# 17_FE_PORT_17-24.net
KiCad netlist of a schematic drawn in Altium Designer
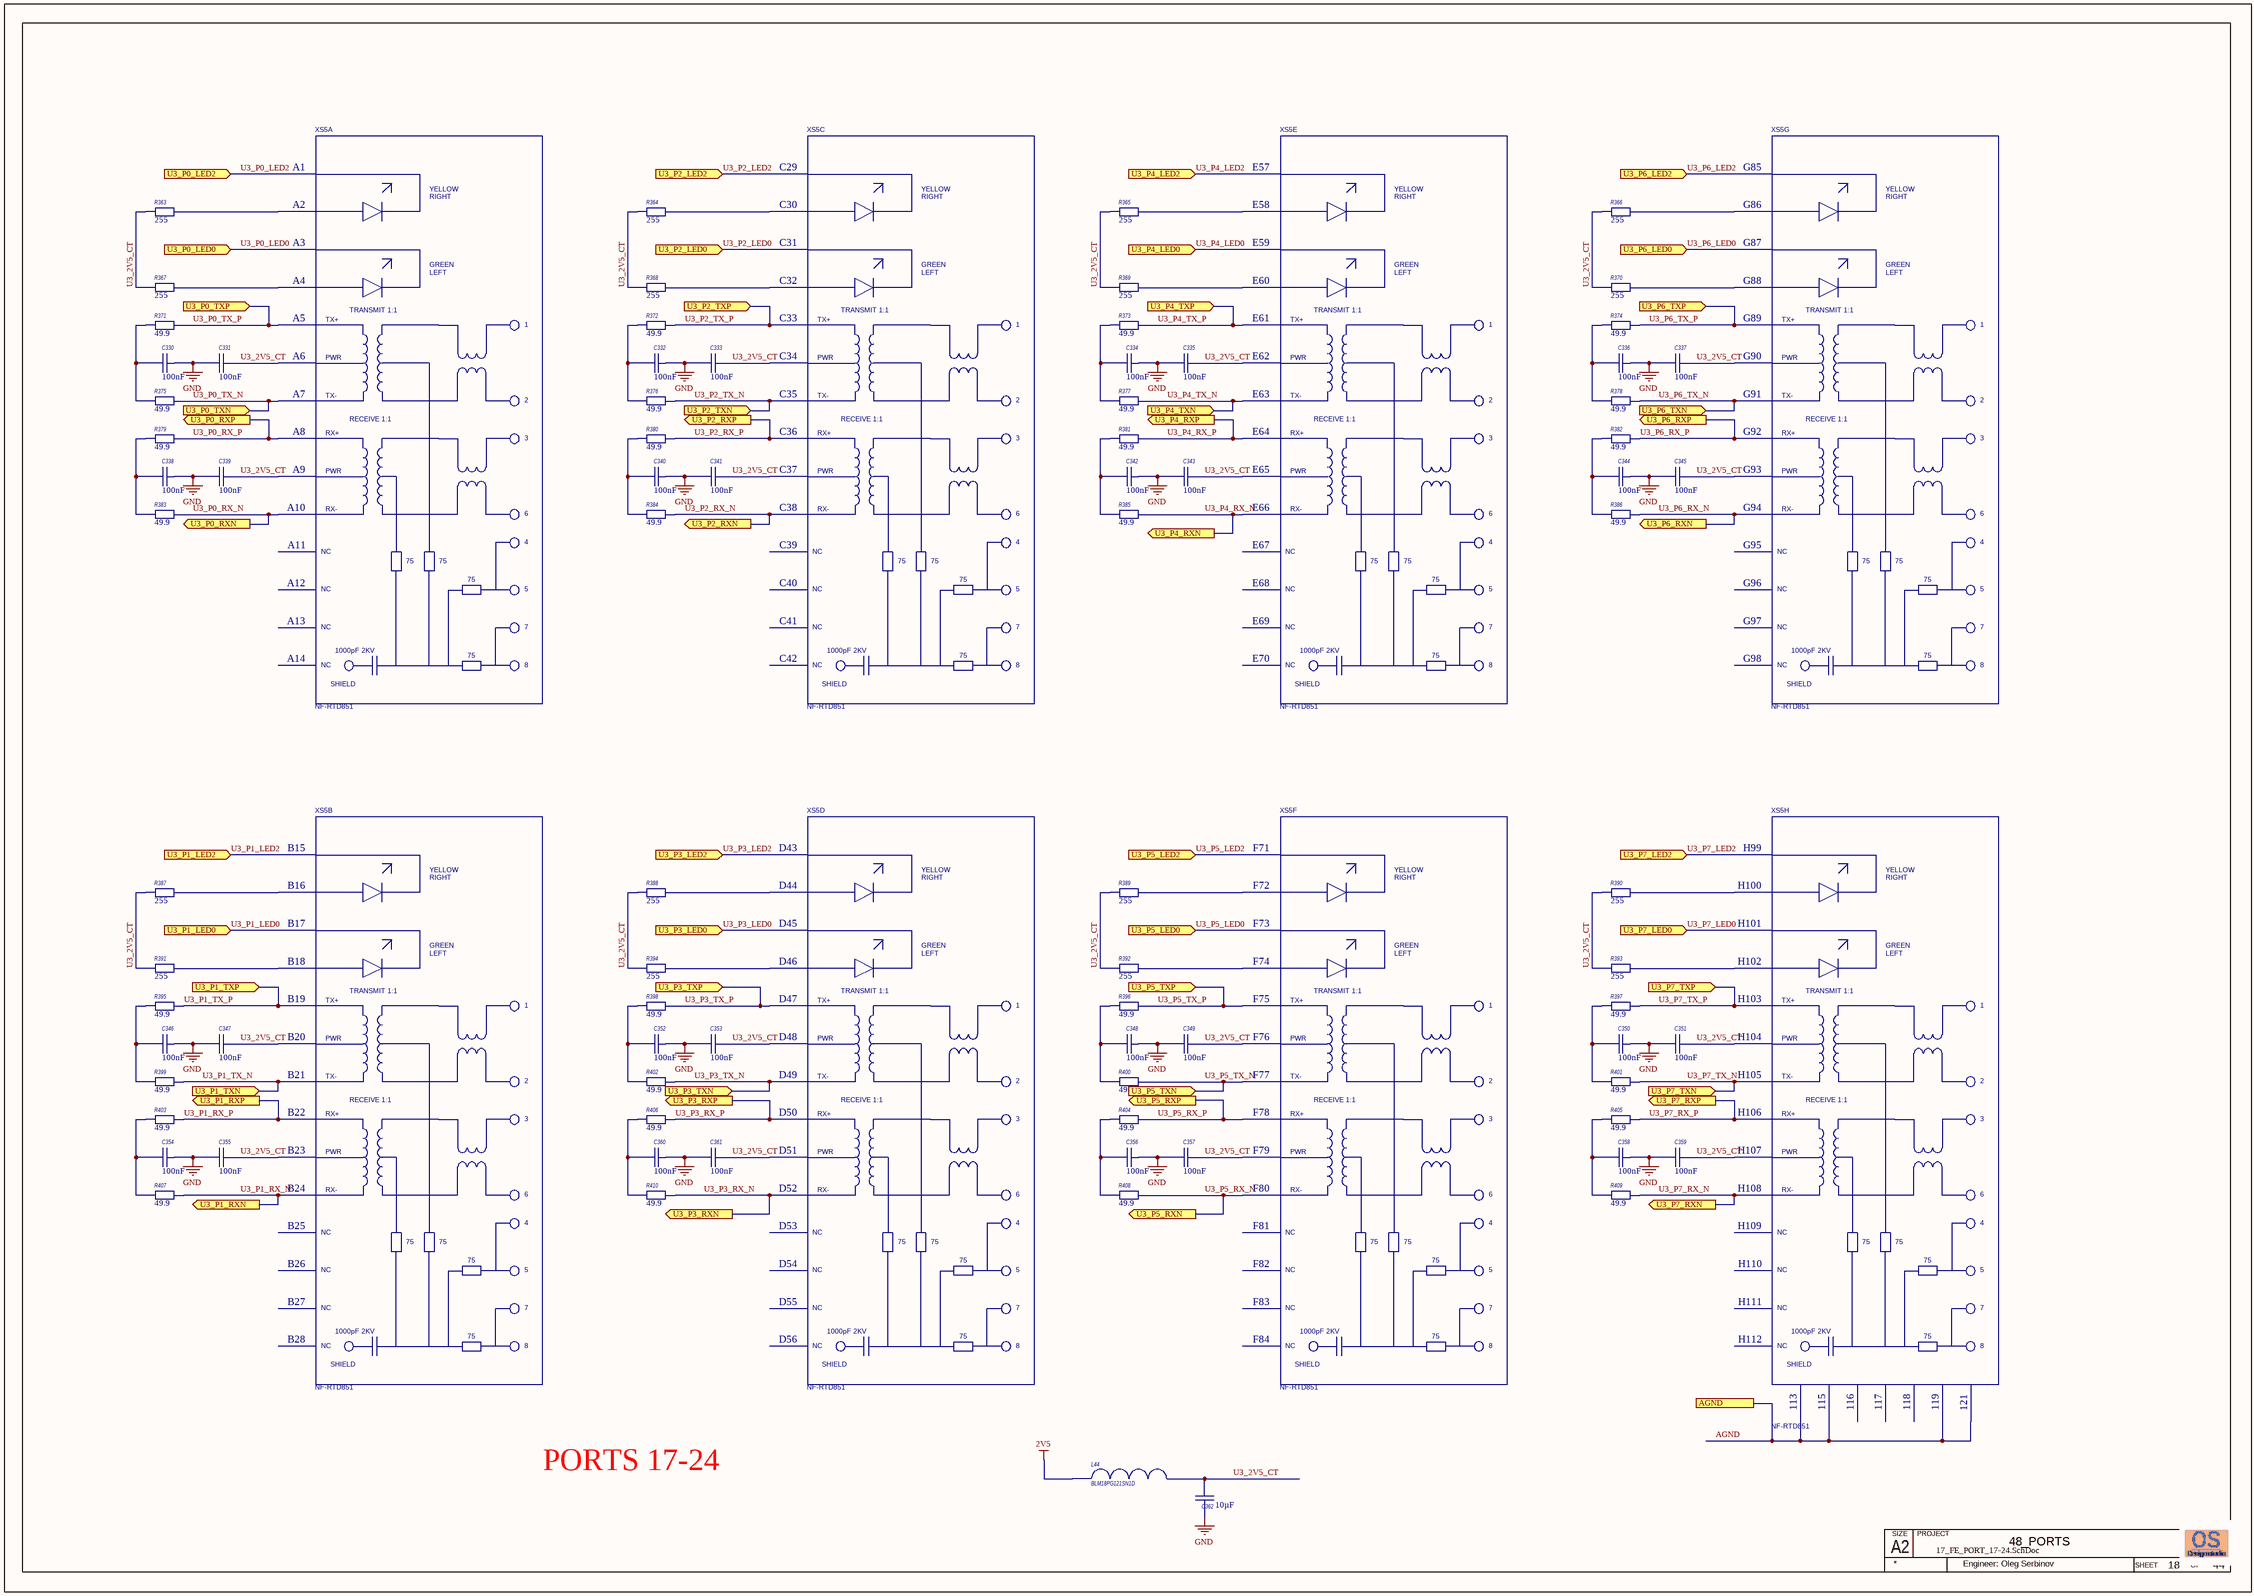
[diagram p0: 17_FE_PORT_17-24.SchDoc]

(export (version "E")
  (design (tool "Eeschema 10.0.6"))
  (components
    (comp (ref "C330")
      (value "GRM155R71E104KE14D")
      (footprint "C0402_IPC High Density")
      (description "C0402, 100nF, 25V, X7R")
      (fields
        (field (name "MANUFACTURER") "Murata")
        (field (name "CAPACITANCE") "100nF")
        (field (name "CUSTOMER PART NUMBER") "Конденсатор, 100n, 0402, 25V, X7R, 10%")
      )
      (libsource (lib "CAPACITORS") (part "GRM155R71E104KE14D"))
    )
    (comp (ref "C331")
      (value "GRM155R71E104KE14D")
      (footprint "C0402_IPC High Density")
      (description "C0402, 100nF, 25V, X7R")
      (fields
        (field (name "MANUFACTURER") "Murata")
        (field (name "CAPACITANCE") "100nF")
        (field (name "CUSTOMER PART NUMBER") "Конденсатор, 100n, 0402, 25V, X7R, 10%")
      )
      (libsource (lib "CAPACITORS") (part "GRM155R71E104KE14D"))
    )
    (comp (ref "C332")
      (value "GRM155R71E104KE14D")
      (footprint "C0402_IPC High Density")
      (description "C0402, 100nF, 25V, X7R")
      (fields
        (field (name "MANUFACTURER") "Murata")
        (field (name "CAPACITANCE") "100nF")
        (field (name "CUSTOMER PART NUMBER") "Конденсатор, 100n, 0402, 25V, X7R, 10%")
      )
      (libsource (lib "CAPACITORS") (part "GRM155R71E104KE14D"))
    )
    (comp (ref "C333")
      (value "GRM155R71E104KE14D")
      (footprint "C0402_IPC High Density")
      (description "C0402, 100nF, 25V, X7R")
      (fields
        (field (name "MANUFACTURER") "Murata")
        (field (name "CAPACITANCE") "100nF")
        (field (name "CUSTOMER PART NUMBER") "Конденсатор, 100n, 0402, 25V, X7R, 10%")
      )
      (libsource (lib "CAPACITORS") (part "GRM155R71E104KE14D"))
    )
    (comp (ref "C334")
      (value "GRM155R71E104KE14D")
      (footprint "C0402_IPC High Density")
      (description "C0402, 100nF, 25V, X7R")
      (fields
        (field (name "MANUFACTURER") "Murata")
        (field (name "CAPACITANCE") "100nF")
        (field (name "CUSTOMER PART NUMBER") "Конденсатор, 100n, 0402, 25V, X7R, 10%")
      )
      (libsource (lib "CAPACITORS") (part "GRM155R71E104KE14D"))
    )
    (comp (ref "C335")
      (value "GRM155R71E104KE14D")
      (footprint "C0402_IPC High Density")
      (description "C0402, 100nF, 25V, X7R")
      (fields
        (field (name "MANUFACTURER") "Murata")
        (field (name "CAPACITANCE") "100nF")
        (field (name "CUSTOMER PART NUMBER") "Конденсатор, 100n, 0402, 25V, X7R, 10%")
      )
      (libsource (lib "CAPACITORS") (part "GRM155R71E104KE14D"))
    )
    (comp (ref "C336")
      (value "GRM155R71E104KE14D")
      (footprint "C0402_IPC High Density")
      (description "C0402, 100nF, 25V, X7R")
      (fields
        (field (name "MANUFACTURER") "Murata")
        (field (name "CAPACITANCE") "100nF")
        (field (name "CUSTOMER PART NUMBER") "Конденсатор, 100n, 0402, 25V, X7R, 10%")
      )
      (libsource (lib "CAPACITORS") (part "GRM155R71E104KE14D"))
    )
    (comp (ref "C337")
      (value "GRM155R71E104KE14D")
      (footprint "C0402_IPC High Density")
      (description "C0402, 100nF, 25V, X7R")
      (fields
        (field (name "MANUFACTURER") "Murata")
        (field (name "CAPACITANCE") "100nF")
        (field (name "CUSTOMER PART NUMBER") "Конденсатор, 100n, 0402, 25V, X7R, 10%")
      )
      (libsource (lib "CAPACITORS") (part "GRM155R71E104KE14D"))
    )
    (comp (ref "C338")
      (value "GRM155R71E104KE14D")
      (footprint "C0402_IPC High Density")
      (description "C0402, 100nF, 25V, X7R")
      (fields
        (field (name "MANUFACTURER") "Murata")
        (field (name "CAPACITANCE") "100nF")
        (field (name "CUSTOMER PART NUMBER") "Конденсатор, 100n, 0402, 25V, X7R, 10%")
      )
      (libsource (lib "CAPACITORS") (part "GRM155R71E104KE14D"))
    )
    (comp (ref "C339")
      (value "GRM155R71E104KE14D")
      (footprint "C0402_IPC High Density")
      (description "C0402, 100nF, 25V, X7R")
      (fields
        (field (name "MANUFACTURER") "Murata")
        (field (name "CAPACITANCE") "100nF")
        (field (name "CUSTOMER PART NUMBER") "Конденсатор, 100n, 0402, 25V, X7R, 10%")
      )
      (libsource (lib "CAPACITORS") (part "GRM155R71E104KE14D"))
    )
    (comp (ref "C340")
      (value "GRM155R71E104KE14D")
      (footprint "C0402_IPC High Density")
      (description "C0402, 100nF, 25V, X7R")
      (fields
        (field (name "MANUFACTURER") "Murata")
        (field (name "CAPACITANCE") "100nF")
        (field (name "CUSTOMER PART NUMBER") "Конденсатор, 100n, 0402, 25V, X7R, 10%")
      )
      (libsource (lib "CAPACITORS") (part "GRM155R71E104KE14D"))
    )
    (comp (ref "C341")
      (value "GRM155R71E104KE14D")
      (footprint "C0402_IPC High Density")
      (description "C0402, 100nF, 25V, X7R")
      (fields
        (field (name "MANUFACTURER") "Murata")
        (field (name "CAPACITANCE") "100nF")
        (field (name "CUSTOMER PART NUMBER") "Конденсатор, 100n, 0402, 25V, X7R, 10%")
      )
      (libsource (lib "CAPACITORS") (part "GRM155R71E104KE14D"))
    )
    (comp (ref "C342")
      (value "GRM155R71E104KE14D")
      (footprint "C0402_IPC High Density")
      (description "C0402, 100nF, 25V, X7R")
      (fields
        (field (name "MANUFACTURER") "Murata")
        (field (name "CAPACITANCE") "100nF")
        (field (name "CUSTOMER PART NUMBER") "Конденсатор, 100n, 0402, 25V, X7R, 10%")
      )
      (libsource (lib "CAPACITORS") (part "GRM155R71E104KE14D"))
    )
    (comp (ref "C343")
      (value "GRM155R71E104KE14D")
      (footprint "C0402_IPC High Density")
      (description "C0402, 100nF, 25V, X7R")
      (fields
        (field (name "MANUFACTURER") "Murata")
        (field (name "CAPACITANCE") "100nF")
        (field (name "CUSTOMER PART NUMBER") "Конденсатор, 100n, 0402, 25V, X7R, 10%")
      )
      (libsource (lib "CAPACITORS") (part "GRM155R71E104KE14D"))
    )
    (comp (ref "C344")
      (value "GRM155R71E104KE14D")
      (footprint "C0402_IPC High Density")
      (description "C0402, 100nF, 25V, X7R")
      (fields
        (field (name "MANUFACTURER") "Murata")
        (field (name "CAPACITANCE") "100nF")
        (field (name "CUSTOMER PART NUMBER") "Конденсатор, 100n, 0402, 25V, X7R, 10%")
      )
      (libsource (lib "CAPACITORS") (part "GRM155R71E104KE14D"))
    )
    (comp (ref "C345")
      (value "GRM155R71E104KE14D")
      (footprint "C0402_IPC High Density")
      (description "C0402, 100nF, 25V, X7R")
      (fields
        (field (name "MANUFACTURER") "Murata")
        (field (name "CAPACITANCE") "100nF")
        (field (name "CUSTOMER PART NUMBER") "Конденсатор, 100n, 0402, 25V, X7R, 10%")
      )
      (libsource (lib "CAPACITORS") (part "GRM155R71E104KE14D"))
    )
    (comp (ref "C346")
      (value "GRM155R71E104KE14D")
      (footprint "C0402_IPC High Density")
      (description "C0402, 100nF, 25V, X7R")
      (fields
        (field (name "MANUFACTURER") "Murata")
        (field (name "CAPACITANCE") "100nF")
        (field (name "CUSTOMER PART NUMBER") "Конденсатор, 100n, 0402, 25V, X7R, 10%")
      )
      (libsource (lib "CAPACITORS") (part "GRM155R71E104KE14D"))
    )
    (comp (ref "C347")
      (value "GRM155R71E104KE14D")
      (footprint "C0402_IPC High Density")
      (description "C0402, 100nF, 25V, X7R")
      (fields
        (field (name "MANUFACTURER") "Murata")
        (field (name "CAPACITANCE") "100nF")
        (field (name "CUSTOMER PART NUMBER") "Конденсатор, 100n, 0402, 25V, X7R, 10%")
      )
      (libsource (lib "CAPACITORS") (part "GRM155R71E104KE14D"))
    )
    (comp (ref "C348")
      (value "GRM155R71E104KE14D")
      (footprint "C0402_IPC High Density")
      (description "C0402, 100nF, 25V, X7R")
      (fields
        (field (name "MANUFACTURER") "Murata")
        (field (name "CAPACITANCE") "100nF")
        (field (name "CUSTOMER PART NUMBER") "Конденсатор, 100n, 0402, 25V, X7R, 10%")
      )
      (libsource (lib "CAPACITORS") (part "GRM155R71E104KE14D"))
    )
    (comp (ref "C349")
      (value "GRM155R71E104KE14D")
      (footprint "C0402_IPC High Density")
      (description "C0402, 100nF, 25V, X7R")
      (fields
        (field (name "MANUFACTURER") "Murata")
        (field (name "CAPACITANCE") "100nF")
        (field (name "CUSTOMER PART NUMBER") "Конденсатор, 100n, 0402, 25V, X7R, 10%")
      )
      (libsource (lib "CAPACITORS") (part "GRM155R71E104KE14D"))
    )
    (comp (ref "C350")
      (value "GRM155R71E104KE14D")
      (footprint "C0402_IPC High Density")
      (description "C0402, 100nF, 25V, X7R")
      (fields
        (field (name "MANUFACTURER") "Murata")
        (field (name "CAPACITANCE") "100nF")
        (field (name "CUSTOMER PART NUMBER") "Конденсатор, 100n, 0402, 25V, X7R, 10%")
      )
      (libsource (lib "CAPACITORS") (part "GRM155R71E104KE14D"))
    )
    (comp (ref "C351")
      (value "GRM155R71E104KE14D")
      (footprint "C0402_IPC High Density")
      (description "C0402, 100nF, 25V, X7R")
      (fields
        (field (name "MANUFACTURER") "Murata")
        (field (name "CAPACITANCE") "100nF")
        (field (name "CUSTOMER PART NUMBER") "Конденсатор, 100n, 0402, 25V, X7R, 10%")
      )
      (libsource (lib "CAPACITORS") (part "GRM155R71E104KE14D"))
    )
    (comp (ref "C352")
      (value "GRM155R71E104KE14D")
      (footprint "C0402_IPC High Density")
      (description "C0402, 100nF, 25V, X7R")
      (fields
        (field (name "MANUFACTURER") "Murata")
        (field (name "CAPACITANCE") "100nF")
        (field (name "CUSTOMER PART NUMBER") "Конденсатор, 100n, 0402, 25V, X7R, 10%")
      )
      (libsource (lib "CAPACITORS") (part "GRM155R71E104KE14D"))
    )
    (comp (ref "C353")
      (value "GRM155R71E104KE14D")
      (footprint "C0402_IPC High Density")
      (description "C0402, 100nF, 25V, X7R")
      (fields
        (field (name "MANUFACTURER") "Murata")
        (field (name "CAPACITANCE") "100nF")
        (field (name "CUSTOMER PART NUMBER") "Конденсатор, 100n, 0402, 25V, X7R, 10%")
      )
      (libsource (lib "CAPACITORS") (part "GRM155R71E104KE14D"))
    )
    (comp (ref "C354")
      (value "GRM155R71E104KE14D")
      (footprint "C0402_IPC High Density")
      (description "C0402, 100nF, 25V, X7R")
      (fields
        (field (name "MANUFACTURER") "Murata")
        (field (name "CAPACITANCE") "100nF")
        (field (name "CUSTOMER PART NUMBER") "Конденсатор, 100n, 0402, 25V, X7R, 10%")
      )
      (libsource (lib "CAPACITORS") (part "GRM155R71E104KE14D"))
    )
    (comp (ref "C355")
      (value "GRM155R71E104KE14D")
      (footprint "C0402_IPC High Density")
      (description "C0402, 100nF, 25V, X7R")
      (fields
        (field (name "MANUFACTURER") "Murata")
        (field (name "CAPACITANCE") "100nF")
        (field (name "CUSTOMER PART NUMBER") "Конденсатор, 100n, 0402, 25V, X7R, 10%")
      )
      (libsource (lib "CAPACITORS") (part "GRM155R71E104KE14D"))
    )
    (comp (ref "C356")
      (value "GRM155R71E104KE14D")
      (footprint "C0402_IPC High Density")
      (description "C0402, 100nF, 25V, X7R")
      (fields
        (field (name "MANUFACTURER") "Murata")
        (field (name "CAPACITANCE") "100nF")
        (field (name "CUSTOMER PART NUMBER") "Конденсатор, 100n, 0402, 25V, X7R, 10%")
      )
      (libsource (lib "CAPACITORS") (part "GRM155R71E104KE14D"))
    )
    (comp (ref "C357")
      (value "GRM155R71E104KE14D")
      (footprint "C0402_IPC High Density")
      (description "C0402, 100nF, 25V, X7R")
      (fields
        (field (name "MANUFACTURER") "Murata")
        (field (name "CAPACITANCE") "100nF")
        (field (name "CUSTOMER PART NUMBER") "Конденсатор, 100n, 0402, 25V, X7R, 10%")
      )
      (libsource (lib "CAPACITORS") (part "GRM155R71E104KE14D"))
    )
    (comp (ref "C358")
      (value "GRM155R71E104KE14D")
      (footprint "C0402_IPC High Density")
      (description "C0402, 100nF, 25V, X7R")
      (fields
        (field (name "MANUFACTURER") "Murata")
        (field (name "CAPACITANCE") "100nF")
        (field (name "CUSTOMER PART NUMBER") "Конденсатор, 100n, 0402, 25V, X7R, 10%")
      )
      (libsource (lib "CAPACITORS") (part "GRM155R71E104KE14D"))
    )
    (comp (ref "C359")
      (value "GRM155R71E104KE14D")
      (footprint "C0402_IPC High Density")
      (description "C0402, 100nF, 25V, X7R")
      (fields
        (field (name "MANUFACTURER") "Murata")
        (field (name "CAPACITANCE") "100nF")
        (field (name "CUSTOMER PART NUMBER") "Конденсатор, 100n, 0402, 25V, X7R, 10%")
      )
      (libsource (lib "CAPACITORS") (part "GRM155R71E104KE14D"))
    )
    (comp (ref "C360")
      (value "GRM155R71E104KE14D")
      (footprint "C0402_IPC High Density")
      (description "C0402, 100nF, 25V, X7R")
      (fields
        (field (name "MANUFACTURER") "Murata")
        (field (name "CAPACITANCE") "100nF")
        (field (name "CUSTOMER PART NUMBER") "Конденсатор, 100n, 0402, 25V, X7R, 10%")
      )
      (libsource (lib "CAPACITORS") (part "GRM155R71E104KE14D"))
    )
    (comp (ref "C361")
      (value "GRM155R71E104KE14D")
      (footprint "C0402_IPC High Density")
      (description "C0402, 100nF, 25V, X7R")
      (fields
        (field (name "MANUFACTURER") "Murata")
        (field (name "CAPACITANCE") "100nF")
        (field (name "CUSTOMER PART NUMBER") "Конденсатор, 100n, 0402, 25V, X7R, 10%")
      )
      (libsource (lib "CAPACITORS") (part "GRM155R71E104KE14D"))
    )
    (comp (ref "C362")
      (value "GRM21BR61C106KE15")
      (footprint "CAPC2012[0805]")
      (description "C0805, 10uF 10%, 16V, X5R")
      (fields
        (field (name "MANUFACTURER") "Murata")
        (field (name "TOLERANCE") "±10%")
        (field (name "CAPACITANCE") "10µF")
      )
      (libsource (lib "CAPACITORS") (part "GRM21BR61C106KE15"))
    )
    (comp (ref "L44")
      (value "BLM18PG121SN1D")
      (footprint "INDC1608X95N")
      (description "FILTER BLM18 (0603, 2A)")
      (fields
        (field (name "MANUFACTURER") "Murata")
        (field (name "RPART NUMBER") "MPZ1608S121ATAH0 ; CIC10P121NC ; MPZ1608S121ATDH5 ; BLM18PG121SH1D ; 742792625")
      )
      (libsource (lib "INDUCTORS") (part "BLM18PG121SN1D"))
    )
    (comp (ref "R363")
      (value "ERJ-2RKF2550X")
      (footprint "RESC1005[0402]")
      (description "R0402, 255R 1%")
      (fields
        (field (name "MANUFACTURER") "Panasonic")
        (field (name "TOLERANCE") "±1%")
        (field (name "RESISTANCE (OHMS)") "255")
      )
      (libsource (lib "RESISTOR") (part "ERJ-2RKF2550X"))
    )
    (comp (ref "R364")
      (value "ERJ-2RKF2550X")
      (footprint "RESC1005[0402]")
      (description "R0402, 255R 1%")
      (fields
        (field (name "MANUFACTURER") "Panasonic")
        (field (name "TOLERANCE") "±1%")
        (field (name "RESISTANCE (OHMS)") "255")
      )
      (libsource (lib "RESISTOR") (part "ERJ-2RKF2550X"))
    )
    (comp (ref "R365")
      (value "ERJ-2RKF2550X")
      (footprint "RESC1005[0402]")
      (description "R0402, 255R 1%")
      (fields
        (field (name "MANUFACTURER") "Panasonic")
        (field (name "TOLERANCE") "±1%")
        (field (name "RESISTANCE (OHMS)") "255")
      )
      (libsource (lib "RESISTOR") (part "ERJ-2RKF2550X"))
    )
    (comp (ref "R366")
      (value "ERJ-2RKF2550X")
      (footprint "RESC1005[0402]")
      (description "R0402, 255R 1%")
      (fields
        (field (name "MANUFACTURER") "Panasonic")
        (field (name "TOLERANCE") "±1%")
        (field (name "RESISTANCE (OHMS)") "255")
      )
      (libsource (lib "RESISTOR") (part "ERJ-2RKF2550X"))
    )
    (comp (ref "R367")
      (value "ERJ-2RKF2550X")
      (footprint "RESC1005[0402]")
      (description "R0402, 255R 1%")
      (fields
        (field (name "MANUFACTURER") "Panasonic")
        (field (name "TOLERANCE") "±1%")
        (field (name "RESISTANCE (OHMS)") "255")
      )
      (libsource (lib "RESISTOR") (part "ERJ-2RKF2550X"))
    )
    (comp (ref "R368")
      (value "ERJ-2RKF2550X")
      (footprint "RESC1005[0402]")
      (description "R0402, 255R 1%")
      (fields
        (field (name "MANUFACTURER") "Panasonic")
        (field (name "TOLERANCE") "±1%")
        (field (name "RESISTANCE (OHMS)") "255")
      )
      (libsource (lib "RESISTOR") (part "ERJ-2RKF2550X"))
    )
    (comp (ref "R369")
      (value "ERJ-2RKF2550X")
      (footprint "RESC1005[0402]")
      (description "R0402, 255R 1%")
      (fields
        (field (name "MANUFACTURER") "Panasonic")
        (field (name "TOLERANCE") "±1%")
        (field (name "RESISTANCE (OHMS)") "255")
      )
      (libsource (lib "RESISTOR") (part "ERJ-2RKF2550X"))
    )
    (comp (ref "R370")
      (value "ERJ-2RKF2550X")
      (footprint "RESC1005[0402]")
      (description "R0402, 255R 1%")
      (fields
        (field (name "MANUFACTURER") "Panasonic")
        (field (name "TOLERANCE") "±1%")
        (field (name "RESISTANCE (OHMS)") "255")
      )
      (libsource (lib "RESISTOR") (part "ERJ-2RKF2550X"))
    )
    (comp (ref "R371")
      (value "ERJ-2RKF49R9X")
      (footprint "R0402_IPC High Density")
      (description "R0402, 49.9R 1%")
      (fields
        (field (name "MANUFACTURER") "Panasonic")
        (field (name "TOLERANCE") "1 %")
        (field (name "RESISTANCE") "49.9")
      )
      (libsource (lib "RESISTOR") (part "ERJ-2RKF49R9X"))
    )
    (comp (ref "R372")
      (value "ERJ-2RKF49R9X")
      (footprint "R0402_IPC High Density")
      (description "R0402, 49.9R 1%")
      (fields
        (field (name "MANUFACTURER") "Panasonic")
        (field (name "TOLERANCE") "1 %")
        (field (name "RESISTANCE") "49.9")
      )
      (libsource (lib "RESISTOR") (part "ERJ-2RKF49R9X"))
    )
    (comp (ref "R373")
      (value "ERJ-2RKF49R9X")
      (footprint "R0402_IPC High Density")
      (description "R0402, 49.9R 1%")
      (fields
        (field (name "MANUFACTURER") "Panasonic")
        (field (name "TOLERANCE") "1 %")
        (field (name "RESISTANCE") "49.9")
      )
      (libsource (lib "RESISTOR") (part "ERJ-2RKF49R9X"))
    )
    (comp (ref "R374")
      (value "ERJ-2RKF49R9X")
      (footprint "R0402_IPC High Density")
      (description "R0402, 49.9R 1%")
      (fields
        (field (name "MANUFACTURER") "Panasonic")
        (field (name "TOLERANCE") "1 %")
        (field (name "RESISTANCE") "49.9")
      )
      (libsource (lib "RESISTOR") (part "ERJ-2RKF49R9X"))
    )
    (comp (ref "R375")
      (value "ERJ-2RKF49R9X")
      (footprint "R0402_IPC High Density")
      (description "R0402, 49.9R 1%")
      (fields
        (field (name "MANUFACTURER") "Panasonic")
        (field (name "TOLERANCE") "1 %")
        (field (name "RESISTANCE") "49.9")
      )
      (libsource (lib "RESISTOR") (part "ERJ-2RKF49R9X"))
    )
    (comp (ref "R376")
      (value "ERJ-2RKF49R9X")
      (footprint "R0402_IPC High Density")
      (description "R0402, 49.9R 1%")
      (fields
        (field (name "MANUFACTURER") "Panasonic")
        (field (name "TOLERANCE") "1 %")
        (field (name "RESISTANCE") "49.9")
      )
      (libsource (lib "RESISTOR") (part "ERJ-2RKF49R9X"))
    )
    (comp (ref "R377")
      (value "ERJ-2RKF49R9X")
      (footprint "R0402_IPC High Density")
      (description "R0402, 49.9R 1%")
      (fields
        (field (name "MANUFACTURER") "Panasonic")
        (field (name "TOLERANCE") "1 %")
        (field (name "RESISTANCE") "49.9")
      )
      (libsource (lib "RESISTOR") (part "ERJ-2RKF49R9X"))
    )
    (comp (ref "R378")
      (value "ERJ-2RKF49R9X")
      (footprint "R0402_IPC High Density")
      (description "R0402, 49.9R 1%")
      (fields
        (field (name "MANUFACTURER") "Panasonic")
        (field (name "TOLERANCE") "1 %")
        (field (name "RESISTANCE") "49.9")
      )
      (libsource (lib "RESISTOR") (part "ERJ-2RKF49R9X"))
    )
    (comp (ref "R379")
      (value "ERJ-2RKF49R9X")
      (footprint "R0402_IPC High Density")
      (description "R0402, 49.9R 1%")
      (fields
        (field (name "MANUFACTURER") "Panasonic")
        (field (name "TOLERANCE") "1 %")
        (field (name "RESISTANCE") "49.9")
      )
      (libsource (lib "RESISTOR") (part "ERJ-2RKF49R9X"))
    )
    (comp (ref "R380")
      (value "ERJ-2RKF49R9X")
      (footprint "R0402_IPC High Density")
      (description "R0402, 49.9R 1%")
      (fields
        (field (name "MANUFACTURER") "Panasonic")
        (field (name "TOLERANCE") "1 %")
        (field (name "RESISTANCE") "49.9")
      )
      (libsource (lib "RESISTOR") (part "ERJ-2RKF49R9X"))
    )
    (comp (ref "R381")
      (value "ERJ-2RKF49R9X")
      (footprint "R0402_IPC High Density")
      (description "R0402, 49.9R 1%")
      (fields
        (field (name "MANUFACTURER") "Panasonic")
        (field (name "TOLERANCE") "1 %")
        (field (name "RESISTANCE") "49.9")
      )
      (libsource (lib "RESISTOR") (part "ERJ-2RKF49R9X"))
    )
    (comp (ref "R382")
      (value "ERJ-2RKF49R9X")
      (footprint "R0402_IPC High Density")
      (description "R0402, 49.9R 1%")
      (fields
        (field (name "MANUFACTURER") "Panasonic")
        (field (name "TOLERANCE") "1 %")
        (field (name "RESISTANCE") "49.9")
      )
      (libsource (lib "RESISTOR") (part "ERJ-2RKF49R9X"))
    )
    (comp (ref "R383")
      (value "ERJ-2RKF49R9X")
      (footprint "R0402_IPC High Density")
      (description "R0402, 49.9R 1%")
      (fields
        (field (name "MANUFACTURER") "Panasonic")
        (field (name "TOLERANCE") "1 %")
        (field (name "RESISTANCE") "49.9")
      )
      (libsource (lib "RESISTOR") (part "ERJ-2RKF49R9X"))
    )
    (comp (ref "R384")
      (value "ERJ-2RKF49R9X")
      (footprint "R0402_IPC High Density")
      (description "R0402, 49.9R 1%")
      (fields
        (field (name "MANUFACTURER") "Panasonic")
        (field (name "TOLERANCE") "1 %")
        (field (name "RESISTANCE") "49.9")
      )
      (libsource (lib "RESISTOR") (part "ERJ-2RKF49R9X"))
    )
    (comp (ref "R385")
      (value "ERJ-2RKF49R9X")
      (footprint "R0402_IPC High Density")
      (description "R0402, 49.9R 1%")
      (fields
        (field (name "MANUFACTURER") "Panasonic")
        (field (name "TOLERANCE") "1 %")
        (field (name "RESISTANCE") "49.9")
      )
      (libsource (lib "RESISTOR") (part "ERJ-2RKF49R9X"))
    )
    (comp (ref "R386")
      (value "ERJ-2RKF49R9X")
      (footprint "R0402_IPC High Density")
      (description "R0402, 49.9R 1%")
      (fields
        (field (name "MANUFACTURER") "Panasonic")
        (field (name "TOLERANCE") "1 %")
        (field (name "RESISTANCE") "49.9")
      )
      (libsource (lib "RESISTOR") (part "ERJ-2RKF49R9X"))
    )
    (comp (ref "R387")
      (value "ERJ-2RKF2550X")
      (footprint "RESC1005[0402]")
      (description "R0402, 255R 1%")
      (fields
        (field (name "MANUFACTURER") "Panasonic")
        (field (name "TOLERANCE") "±1%")
        (field (name "RESISTANCE (OHMS)") "255")
      )
      (libsource (lib "RESISTOR") (part "ERJ-2RKF2550X"))
    )
    (comp (ref "R388")
      (value "ERJ-2RKF2550X")
      (footprint "RESC1005[0402]")
      (description "R0402, 255R 1%")
      (fields
        (field (name "MANUFACTURER") "Panasonic")
        (field (name "TOLERANCE") "±1%")
        (field (name "RESISTANCE (OHMS)") "255")
      )
      (libsource (lib "RESISTOR") (part "ERJ-2RKF2550X"))
    )
    (comp (ref "R389")
      (value "ERJ-2RKF2550X")
      (footprint "RESC1005[0402]")
      (description "R0402, 255R 1%")
      (fields
        (field (name "MANUFACTURER") "Panasonic")
        (field (name "TOLERANCE") "±1%")
        (field (name "RESISTANCE (OHMS)") "255")
      )
      (libsource (lib "RESISTOR") (part "ERJ-2RKF2550X"))
    )
    (comp (ref "R390")
      (value "ERJ-2RKF2550X")
      (footprint "RESC1005[0402]")
      (description "R0402, 255R 1%")
      (fields
        (field (name "MANUFACTURER") "Panasonic")
        (field (name "TOLERANCE") "±1%")
        (field (name "RESISTANCE (OHMS)") "255")
      )
      (libsource (lib "RESISTOR") (part "ERJ-2RKF2550X"))
    )
    (comp (ref "R391")
      (value "ERJ-2RKF2550X")
      (footprint "RESC1005[0402]")
      (description "R0402, 255R 1%")
      (fields
        (field (name "MANUFACTURER") "Panasonic")
        (field (name "TOLERANCE") "±1%")
        (field (name "RESISTANCE (OHMS)") "255")
      )
      (libsource (lib "RESISTOR") (part "ERJ-2RKF2550X"))
    )
    (comp (ref "R392")
      (value "ERJ-2RKF2550X")
      (footprint "RESC1005[0402]")
      (description "R0402, 255R 1%")
      (fields
        (field (name "MANUFACTURER") "Panasonic")
        (field (name "TOLERANCE") "±1%")
        (field (name "RESISTANCE (OHMS)") "255")
      )
      (libsource (lib "RESISTOR") (part "ERJ-2RKF2550X"))
    )
    (comp (ref "R393")
      (value "ERJ-2RKF2550X")
      (footprint "RESC1005[0402]")
      (description "R0402, 255R 1%")
      (fields
        (field (name "MANUFACTURER") "Panasonic")
        (field (name "TOLERANCE") "±1%")
        (field (name "RESISTANCE (OHMS)") "255")
      )
      (libsource (lib "RESISTOR") (part "ERJ-2RKF2550X"))
    )
    (comp (ref "R394")
      (value "ERJ-2RKF2550X")
      (footprint "RESC1005[0402]")
      (description "R0402, 255R 1%")
      (fields
        (field (name "MANUFACTURER") "Panasonic")
        (field (name "TOLERANCE") "±1%")
        (field (name "RESISTANCE (OHMS)") "255")
      )
      (libsource (lib "RESISTOR") (part "ERJ-2RKF2550X"))
    )
    (comp (ref "R395")
      (value "ERJ-2RKF49R9X")
      (footprint "R0402_IPC High Density")
      (description "R0402, 49.9R 1%")
      (fields
        (field (name "MANUFACTURER") "Panasonic")
        (field (name "TOLERANCE") "1 %")
        (field (name "RESISTANCE") "49.9")
      )
      (libsource (lib "RESISTOR") (part "ERJ-2RKF49R9X"))
    )
    (comp (ref "R396")
      (value "ERJ-2RKF49R9X")
      (footprint "R0402_IPC High Density")
      (description "R0402, 49.9R 1%")
      (fields
        (field (name "MANUFACTURER") "Panasonic")
        (field (name "TOLERANCE") "1 %")
        (field (name "RESISTANCE") "49.9")
      )
      (libsource (lib "RESISTOR") (part "ERJ-2RKF49R9X"))
    )
    (comp (ref "R397")
      (value "ERJ-2RKF49R9X")
      (footprint "R0402_IPC High Density")
      (description "R0402, 49.9R 1%")
      (fields
        (field (name "MANUFACTURER") "Panasonic")
        (field (name "TOLERANCE") "1 %")
        (field (name "RESISTANCE") "49.9")
      )
      (libsource (lib "RESISTOR") (part "ERJ-2RKF49R9X"))
    )
    (comp (ref "R398")
      (value "ERJ-2RKF49R9X")
      (footprint "R0402_IPC High Density")
      (description "R0402, 49.9R 1%")
      (fields
        (field (name "MANUFACTURER") "Panasonic")
        (field (name "TOLERANCE") "1 %")
        (field (name "RESISTANCE") "49.9")
      )
      (libsource (lib "RESISTOR") (part "ERJ-2RKF49R9X"))
    )
    (comp (ref "R399")
      (value "ERJ-2RKF49R9X")
      (footprint "R0402_IPC High Density")
      (description "R0402, 49.9R 1%")
      (fields
        (field (name "MANUFACTURER") "Panasonic")
        (field (name "TOLERANCE") "1 %")
        (field (name "RESISTANCE") "49.9")
      )
      (libsource (lib "RESISTOR") (part "ERJ-2RKF49R9X"))
    )
    (comp (ref "R400")
      (value "ERJ-2RKF49R9X")
      (footprint "R0402_IPC High Density")
      (description "R0402, 49.9R 1%")
      (fields
        (field (name "MANUFACTURER") "Panasonic")
        (field (name "TOLERANCE") "1 %")
        (field (name "RESISTANCE") "49.9")
      )
      (libsource (lib "RESISTOR") (part "ERJ-2RKF49R9X"))
    )
    (comp (ref "R401")
      (value "ERJ-2RKF49R9X")
      (footprint "R0402_IPC High Density")
      (description "R0402, 49.9R 1%")
      (fields
        (field (name "MANUFACTURER") "Panasonic")
        (field (name "TOLERANCE") "1 %")
        (field (name "RESISTANCE") "49.9")
      )
      (libsource (lib "RESISTOR") (part "ERJ-2RKF49R9X"))
    )
    (comp (ref "R402")
      (value "ERJ-2RKF49R9X")
      (footprint "R0402_IPC High Density")
      (description "R0402, 49.9R 1%")
      (fields
        (field (name "MANUFACTURER") "Panasonic")
        (field (name "TOLERANCE") "1 %")
        (field (name "RESISTANCE") "49.9")
      )
      (libsource (lib "RESISTOR") (part "ERJ-2RKF49R9X"))
    )
    (comp (ref "R403")
      (value "ERJ-2RKF49R9X")
      (footprint "R0402_IPC High Density")
      (description "R0402, 49.9R 1%")
      (fields
        (field (name "MANUFACTURER") "Panasonic")
        (field (name "TOLERANCE") "1 %")
        (field (name "RESISTANCE") "49.9")
      )
      (libsource (lib "RESISTOR") (part "ERJ-2RKF49R9X"))
    )
    (comp (ref "R404")
      (value "ERJ-2RKF49R9X")
      (footprint "R0402_IPC High Density")
      (description "R0402, 49.9R 1%")
      (fields
        (field (name "MANUFACTURER") "Panasonic")
        (field (name "TOLERANCE") "1 %")
        (field (name "RESISTANCE") "49.9")
      )
      (libsource (lib "RESISTOR") (part "ERJ-2RKF49R9X"))
    )
    (comp (ref "R405")
      (value "ERJ-2RKF49R9X")
      (footprint "R0402_IPC High Density")
      (description "R0402, 49.9R 1%")
      (fields
        (field (name "MANUFACTURER") "Panasonic")
        (field (name "TOLERANCE") "1 %")
        (field (name "RESISTANCE") "49.9")
      )
      (libsource (lib "RESISTOR") (part "ERJ-2RKF49R9X"))
    )
    (comp (ref "R406")
      (value "ERJ-2RKF49R9X")
      (footprint "R0402_IPC High Density")
      (description "R0402, 49.9R 1%")
      (fields
        (field (name "MANUFACTURER") "Panasonic")
        (field (name "TOLERANCE") "1 %")
        (field (name "RESISTANCE") "49.9")
      )
      (libsource (lib "RESISTOR") (part "ERJ-2RKF49R9X"))
    )
    (comp (ref "R407")
      (value "ERJ-2RKF49R9X")
      (footprint "R0402_IPC High Density")
      (description "R0402, 49.9R 1%")
      (fields
        (field (name "MANUFACTURER") "Panasonic")
        (field (name "TOLERANCE") "1 %")
        (field (name "RESISTANCE") "49.9")
      )
      (libsource (lib "RESISTOR") (part "ERJ-2RKF49R9X"))
    )
    (comp (ref "R408")
      (value "ERJ-2RKF49R9X")
      (footprint "R0402_IPC High Density")
      (description "R0402, 49.9R 1%")
      (fields
        (field (name "MANUFACTURER") "Panasonic")
        (field (name "TOLERANCE") "1 %")
        (field (name "RESISTANCE") "49.9")
      )
      (libsource (lib "RESISTOR") (part "ERJ-2RKF49R9X"))
    )
    (comp (ref "R409")
      (value "ERJ-2RKF49R9X")
      (footprint "R0402_IPC High Density")
      (description "R0402, 49.9R 1%")
      (fields
        (field (name "MANUFACTURER") "Panasonic")
        (field (name "TOLERANCE") "1 %")
        (field (name "RESISTANCE") "49.9")
      )
      (libsource (lib "RESISTOR") (part "ERJ-2RKF49R9X"))
    )
    (comp (ref "R410")
      (value "ERJ-2RKF49R9X")
      (footprint "R0402_IPC High Density")
      (description "R0402, 49.9R 1%")
      (fields
        (field (name "MANUFACTURER") "Panasonic")
        (field (name "TOLERANCE") "1 %")
        (field (name "RESISTANCE") "49.9")
      )
      (libsource (lib "RESISTOR") (part "ERJ-2RKF49R9X"))
    )
    (comp (ref "XS5")
      (value "NF-RTD851")
      (footprint "NF-RTD851_2X4_LED_NF-RTD851_2X4_LED(Primary)")
      (description "Connector RJ45 100mb 8 ports and led  NF-RTD851")
      (fields
        (field (name "CUSTOMER PART NUMBER") "Разъем, NF-RTD851, CONN MAGJACK 8PORT 100 BASE-TX")
        (field (name "MANUFACTURER") "Shenzhen Newfly Electronics")
      )
      (libsource (lib "CONNECTORS") (part "NF-RTD851 2X4 EMI LED"))
    )
  )
  (nets
    (net (code "1") (name "/AGND") (class "Default")
      (node (ref "XS5") (pin "113") (pintype "passive"))
      (node (ref "XS5") (pin "115") (pintype "passive"))
      (node (ref "XS5") (pin "119") (pintype "passive"))
      (node (ref "XS5") (pin "121") (pintype "passive"))
    )
    (net (code "2") (name "/U3_2V5_CT") (class "Default")
      (node (ref "C331") (pin "2") (pintype "passive"))
      (node (ref "C333") (pin "2") (pintype "passive"))
      (node (ref "C335") (pin "2") (pintype "passive"))
      (node (ref "C337") (pin "2") (pintype "passive"))
      (node (ref "C339") (pin "2") (pintype "passive"))
      (node (ref "C341") (pin "2") (pintype "passive"))
      (node (ref "C343") (pin "2") (pintype "passive"))
      (node (ref "C345") (pin "2") (pintype "passive"))
      (node (ref "C347") (pin "2") (pintype "passive"))
      (node (ref "C349") (pin "2") (pintype "passive"))
      (node (ref "C351") (pin "2") (pintype "passive"))
      (node (ref "C353") (pin "2") (pintype "passive"))
      (node (ref "C355") (pin "2") (pintype "passive"))
      (node (ref "C357") (pin "2") (pintype "passive"))
      (node (ref "C359") (pin "2") (pintype "passive"))
      (node (ref "C361") (pin "2") (pintype "passive"))
      (node (ref "C362") (pin "2") (pintype "passive"))
      (node (ref "L44") (pin "2") (pinfunction "2_2") (pintype "passive"))
      (node (ref "R363") (pin "1") (pintype "passive"))
      (node (ref "R364") (pin "1") (pintype "passive"))
      (node (ref "R365") (pin "1") (pintype "passive"))
      (node (ref "R366") (pin "1") (pintype "passive"))
      (node (ref "R367") (pin "1") (pintype "passive"))
      (node (ref "R368") (pin "1") (pintype "passive"))
      (node (ref "R369") (pin "1") (pintype "passive"))
      (node (ref "R370") (pin "1") (pintype "passive"))
      (node (ref "R387") (pin "1") (pintype "passive"))
      (node (ref "R388") (pin "1") (pintype "passive"))
      (node (ref "R389") (pin "1") (pintype "passive"))
      (node (ref "R390") (pin "1") (pintype "passive"))
      (node (ref "R391") (pin "1") (pintype "passive"))
      (node (ref "R392") (pin "1") (pintype "passive"))
      (node (ref "R393") (pin "1") (pintype "passive"))
      (node (ref "R394") (pin "1") (pintype "passive"))
      (node (ref "XS5") (pin "A6") (pintype "passive"))
      (node (ref "XS5") (pin "A9") (pintype "passive"))
      (node (ref "XS5") (pin "B20") (pintype "passive"))
      (node (ref "XS5") (pin "B23") (pintype "passive"))
      (node (ref "XS5") (pin "C34") (pintype "passive"))
      (node (ref "XS5") (pin "C37") (pintype "passive"))
      (node (ref "XS5") (pin "D48") (pintype "passive"))
      (node (ref "XS5") (pin "D51") (pintype "passive"))
      (node (ref "XS5") (pin "E62") (pintype "passive"))
      (node (ref "XS5") (pin "E65") (pintype "passive"))
      (node (ref "XS5") (pin "F76") (pintype "passive"))
      (node (ref "XS5") (pin "F79") (pintype "passive"))
      (node (ref "XS5") (pin "G90") (pintype "passive"))
      (node (ref "XS5") (pin "G93") (pintype "passive"))
      (node (ref "XS5") (pin "H104") (pintype "passive"))
      (node (ref "XS5") (pin "H107") (pintype "passive"))
    )
    (net (code "3") (name "/U3_P0_LED0") (class "Default") (node (ref "XS5") (pin "A3") (pintype "passive")))
    (net (code "4") (name "/U3_P0_LED2") (class "Default") (node (ref "XS5") (pin "A1") (pintype "passive")))
    (net (code "5") (name "/U3_P0_RX_N") (class "Default")
      (node (ref "R383") (pin "2") (pintype "passive"))
      (node (ref "XS5") (pin "A10") (pintype "passive"))
    )
    (net (code "6") (name "/U3_P0_RX_P") (class "Default")
      (node (ref "R379") (pin "2") (pintype "passive"))
      (node (ref "XS5") (pin "A8") (pintype "passive"))
    )
    (net (code "7") (name "/U3_P0_TX_N") (class "Default")
      (node (ref "R375") (pin "2") (pintype "passive"))
      (node (ref "XS5") (pin "A7") (pintype "passive"))
    )
    (net (code "8") (name "/U3_P0_TX_P") (class "Default")
      (node (ref "R371") (pin "2") (pintype "passive"))
      (node (ref "XS5") (pin "A5") (pintype "passive"))
    )
    (net (code "9") (name "/U3_P1_LED0") (class "Default") (node (ref "XS5") (pin "B17") (pintype "passive")))
    (net (code "10") (name "/U3_P1_LED2") (class "Default")
      (node (ref "XS5") (pin "B15") (pintype "passive"))
    )
    (net (code "11") (name "/U3_P1_RX_N") (class "Default")
      (node (ref "R407") (pin "2") (pintype "passive"))
      (node (ref "XS5") (pin "B24") (pintype "passive"))
    )
    (net (code "12") (name "/U3_P1_RX_P") (class "Default")
      (node (ref "R403") (pin "2") (pintype "passive"))
      (node (ref "XS5") (pin "B22") (pintype "passive"))
    )
    (net (code "13") (name "/U3_P1_TX_N") (class "Default")
      (node (ref "R399") (pin "2") (pintype "passive"))
      (node (ref "XS5") (pin "B21") (pintype "passive"))
    )
    (net (code "14") (name "/U3_P1_TX_P") (class "Default")
      (node (ref "R395") (pin "2") (pintype "passive"))
      (node (ref "XS5") (pin "B19") (pintype "passive"))
    )
    (net (code "15") (name "/U3_P2_LED0") (class "Default")
      (node (ref "XS5") (pin "C31") (pintype "passive"))
    )
    (net (code "16") (name "/U3_P2_LED2") (class "Default")
      (node (ref "XS5") (pin "C29") (pintype "passive"))
    )
    (net (code "17") (name "/U3_P2_RX_N") (class "Default")
      (node (ref "R384") (pin "2") (pintype "passive"))
      (node (ref "XS5") (pin "C38") (pintype "passive"))
    )
    (net (code "18") (name "/U3_P2_RX_P") (class "Default")
      (node (ref "R380") (pin "2") (pintype "passive"))
      (node (ref "XS5") (pin "C36") (pintype "passive"))
    )
    (net (code "19") (name "/U3_P2_TX_N") (class "Default")
      (node (ref "R376") (pin "2") (pintype "passive"))
      (node (ref "XS5") (pin "C35") (pintype "passive"))
    )
    (net (code "20") (name "/U3_P2_TX_P") (class "Default")
      (node (ref "R372") (pin "2") (pintype "passive"))
      (node (ref "XS5") (pin "C33") (pintype "passive"))
    )
    (net (code "21") (name "/U3_P3_LED0") (class "Default")
      (node (ref "XS5") (pin "D45") (pintype "passive"))
    )
    (net (code "22") (name "/U3_P3_LED2") (class "Default")
      (node (ref "XS5") (pin "D43") (pintype "passive"))
    )
    (net (code "23") (name "/U3_P3_RX_N") (class "Default")
      (node (ref "R410") (pin "2") (pintype "passive"))
      (node (ref "XS5") (pin "D52") (pintype "passive"))
    )
    (net (code "24") (name "/U3_P3_RX_P") (class "Default")
      (node (ref "R406") (pin "2") (pintype "passive"))
      (node (ref "XS5") (pin "D50") (pintype "passive"))
    )
    (net (code "25") (name "/U3_P3_TX_N") (class "Default")
      (node (ref "R402") (pin "2") (pintype "passive"))
      (node (ref "XS5") (pin "D49") (pintype "passive"))
    )
    (net (code "26") (name "/U3_P3_TX_P") (class "Default")
      (node (ref "R398") (pin "2") (pintype "passive"))
      (node (ref "XS5") (pin "D47") (pintype "passive"))
    )
    (net (code "27") (name "/U3_P4_LED0") (class "Default")
      (node (ref "XS5") (pin "E59") (pintype "passive"))
    )
    (net (code "28") (name "/U3_P4_LED2") (class "Default")
      (node (ref "XS5") (pin "E57") (pintype "passive"))
    )
    (net (code "29") (name "/U3_P4_RX_N") (class "Default")
      (node (ref "R385") (pin "2") (pintype "passive"))
      (node (ref "XS5") (pin "E66") (pintype "passive"))
    )
    (net (code "30") (name "/U3_P4_RX_P") (class "Default")
      (node (ref "R381") (pin "2") (pintype "passive"))
      (node (ref "XS5") (pin "E64") (pintype "passive"))
    )
    (net (code "31") (name "/U3_P4_TX_N") (class "Default")
      (node (ref "R377") (pin "2") (pintype "passive"))
      (node (ref "XS5") (pin "E63") (pintype "passive"))
    )
    (net (code "32") (name "/U3_P4_TX_P") (class "Default")
      (node (ref "R373") (pin "2") (pintype "passive"))
      (node (ref "XS5") (pin "E61") (pintype "passive"))
    )
    (net (code "33") (name "/U3_P5_LED0") (class "Default")
      (node (ref "XS5") (pin "F73") (pintype "passive"))
    )
    (net (code "34") (name "/U3_P5_LED2") (class "Default")
      (node (ref "XS5") (pin "F71") (pintype "passive"))
    )
    (net (code "35") (name "/U3_P5_RX_N") (class "Default")
      (node (ref "R408") (pin "2") (pintype "passive"))
      (node (ref "XS5") (pin "F80") (pintype "passive"))
    )
    (net (code "36") (name "/U3_P5_RX_P") (class "Default")
      (node (ref "R404") (pin "2") (pintype "passive"))
      (node (ref "XS5") (pin "F78") (pintype "passive"))
    )
    (net (code "37") (name "/U3_P5_TX_N") (class "Default")
      (node (ref "R400") (pin "2") (pintype "passive"))
      (node (ref "XS5") (pin "F77") (pintype "passive"))
    )
    (net (code "38") (name "/U3_P5_TX_P") (class "Default")
      (node (ref "R396") (pin "2") (pintype "passive"))
      (node (ref "XS5") (pin "F75") (pintype "passive"))
    )
    (net (code "39") (name "/U3_P6_LED0") (class "Default")
      (node (ref "XS5") (pin "G87") (pintype "passive"))
    )
    (net (code "40") (name "/U3_P6_LED2") (class "Default")
      (node (ref "XS5") (pin "G85") (pintype "passive"))
    )
    (net (code "41") (name "/U3_P6_RX_N") (class "Default")
      (node (ref "R386") (pin "2") (pintype "passive"))
      (node (ref "XS5") (pin "G94") (pintype "passive"))
    )
    (net (code "42") (name "/U3_P6_RX_P") (class "Default")
      (node (ref "R382") (pin "2") (pintype "passive"))
      (node (ref "XS5") (pin "G92") (pintype "passive"))
    )
    (net (code "43") (name "/U3_P6_TX_N") (class "Default")
      (node (ref "R378") (pin "2") (pintype "passive"))
      (node (ref "XS5") (pin "G91") (pintype "passive"))
    )
    (net (code "44") (name "/U3_P6_TX_P") (class "Default")
      (node (ref "R374") (pin "2") (pintype "passive"))
      (node (ref "XS5") (pin "G89") (pintype "passive"))
    )
    (net (code "45") (name "/U3_P7_LED0") (class "Default")
      (node (ref "XS5") (pin "H101") (pintype "passive"))
    )
    (net (code "46") (name "/U3_P7_LED2") (class "Default")
      (node (ref "XS5") (pin "H99") (pintype "passive"))
    )
    (net (code "47") (name "/U3_P7_RX_N") (class "Default")
      (node (ref "R409") (pin "2") (pintype "passive"))
      (node (ref "XS5") (pin "H108") (pintype "passive"))
    )
    (net (code "48") (name "/U3_P7_RX_P") (class "Default")
      (node (ref "R405") (pin "2") (pintype "passive"))
      (node (ref "XS5") (pin "H106") (pintype "passive"))
    )
    (net (code "49") (name "/U3_P7_TX_N") (class "Default")
      (node (ref "R401") (pin "2") (pintype "passive"))
      (node (ref "XS5") (pin "H105") (pintype "passive"))
    )
    (net (code "50") (name "/U3_P7_TX_P") (class "Default")
      (node (ref "R397") (pin "2") (pintype "passive"))
      (node (ref "XS5") (pin "H103") (pintype "passive"))
    )
    (net (code "51") (name "2V5") (class "Default")
      (node (ref "L44") (pin "1") (pinfunction "1_1") (pintype "passive"))
    )
    (net (code "52") (name "GND") (class "Default")
      (node (ref "C330") (pin "2") (pintype "passive"))
      (node (ref "C331") (pin "1") (pintype "passive"))
      (node (ref "C332") (pin "2") (pintype "passive"))
      (node (ref "C333") (pin "1") (pintype "passive"))
      (node (ref "C334") (pin "2") (pintype "passive"))
      (node (ref "C335") (pin "1") (pintype "passive"))
      (node (ref "C336") (pin "2") (pintype "passive"))
      (node (ref "C337") (pin "1") (pintype "passive"))
      (node (ref "C338") (pin "2") (pintype "passive"))
      (node (ref "C339") (pin "1") (pintype "passive"))
      (node (ref "C340") (pin "2") (pintype "passive"))
      (node (ref "C341") (pin "1") (pintype "passive"))
      (node (ref "C342") (pin "2") (pintype "passive"))
      (node (ref "C343") (pin "1") (pintype "passive"))
      (node (ref "C344") (pin "2") (pintype "passive"))
      (node (ref "C345") (pin "1") (pintype "passive"))
      (node (ref "C346") (pin "2") (pintype "passive"))
      (node (ref "C347") (pin "1") (pintype "passive"))
      (node (ref "C348") (pin "2") (pintype "passive"))
      (node (ref "C349") (pin "1") (pintype "passive"))
      (node (ref "C350") (pin "2") (pintype "passive"))
      (node (ref "C351") (pin "1") (pintype "passive"))
      (node (ref "C352") (pin "2") (pintype "passive"))
      (node (ref "C353") (pin "1") (pintype "passive"))
      (node (ref "C354") (pin "2") (pintype "passive"))
      (node (ref "C355") (pin "1") (pintype "passive"))
      (node (ref "C356") (pin "2") (pintype "passive"))
      (node (ref "C357") (pin "1") (pintype "passive"))
      (node (ref "C358") (pin "2") (pintype "passive"))
      (node (ref "C359") (pin "1") (pintype "passive"))
      (node (ref "C360") (pin "2") (pintype "passive"))
      (node (ref "C361") (pin "1") (pintype "passive"))
      (node (ref "C362") (pin "1") (pintype "passive"))
    )
    (net (code "53") (name "Net-(C330-Pad1)") (class "Default")
      (node (ref "C330") (pin "1") (pintype "passive"))
      (node (ref "R371") (pin "1") (pintype "passive"))
      (node (ref "R375") (pin "1") (pintype "passive"))
    )
    (net (code "54") (name "Net-(C332-Pad1)") (class "Default")
      (node (ref "C332") (pin "1") (pintype "passive"))
      (node (ref "R372") (pin "1") (pintype "passive"))
      (node (ref "R376") (pin "1") (pintype "passive"))
    )
    (net (code "55") (name "Net-(C334-Pad1)") (class "Default")
      (node (ref "C334") (pin "1") (pintype "passive"))
      (node (ref "R373") (pin "1") (pintype "passive"))
      (node (ref "R377") (pin "1") (pintype "passive"))
    )
    (net (code "56") (name "Net-(C336-Pad1)") (class "Default")
      (node (ref "C336") (pin "1") (pintype "passive"))
      (node (ref "R374") (pin "1") (pintype "passive"))
      (node (ref "R378") (pin "1") (pintype "passive"))
    )
    (net (code "57") (name "Net-(C338-Pad1)") (class "Default")
      (node (ref "C338") (pin "1") (pintype "passive"))
      (node (ref "R379") (pin "1") (pintype "passive"))
      (node (ref "R383") (pin "1") (pintype "passive"))
    )
    (net (code "58") (name "Net-(C340-Pad1)") (class "Default")
      (node (ref "C340") (pin "1") (pintype "passive"))
      (node (ref "R380") (pin "1") (pintype "passive"))
      (node (ref "R384") (pin "1") (pintype "passive"))
    )
    (net (code "59") (name "Net-(C342-Pad1)") (class "Default")
      (node (ref "C342") (pin "1") (pintype "passive"))
      (node (ref "R381") (pin "1") (pintype "passive"))
      (node (ref "R385") (pin "1") (pintype "passive"))
    )
    (net (code "60") (name "Net-(C344-Pad1)") (class "Default")
      (node (ref "C344") (pin "1") (pintype "passive"))
      (node (ref "R382") (pin "1") (pintype "passive"))
      (node (ref "R386") (pin "1") (pintype "passive"))
    )
    (net (code "61") (name "Net-(C346-Pad1)") (class "Default")
      (node (ref "C346") (pin "1") (pintype "passive"))
      (node (ref "R395") (pin "1") (pintype "passive"))
      (node (ref "R399") (pin "1") (pintype "passive"))
    )
    (net (code "62") (name "Net-(C348-Pad1)") (class "Default")
      (node (ref "C348") (pin "1") (pintype "passive"))
      (node (ref "R396") (pin "1") (pintype "passive"))
      (node (ref "R400") (pin "1") (pintype "passive"))
    )
    (net (code "63") (name "Net-(C350-Pad1)") (class "Default")
      (node (ref "C350") (pin "1") (pintype "passive"))
      (node (ref "R397") (pin "1") (pintype "passive"))
      (node (ref "R401") (pin "1") (pintype "passive"))
    )
    (net (code "64") (name "Net-(C352-Pad1)") (class "Default")
      (node (ref "C352") (pin "1") (pintype "passive"))
      (node (ref "R398") (pin "1") (pintype "passive"))
      (node (ref "R402") (pin "1") (pintype "passive"))
    )
    (net (code "65") (name "Net-(C354-Pad1)") (class "Default")
      (node (ref "C354") (pin "1") (pintype "passive"))
      (node (ref "R403") (pin "1") (pintype "passive"))
      (node (ref "R407") (pin "1") (pintype "passive"))
    )
    (net (code "66") (name "Net-(C356-Pad1)") (class "Default")
      (node (ref "C356") (pin "1") (pintype "passive"))
      (node (ref "R404") (pin "1") (pintype "passive"))
      (node (ref "R408") (pin "1") (pintype "passive"))
    )
    (net (code "67") (name "Net-(C358-Pad1)") (class "Default")
      (node (ref "C358") (pin "1") (pintype "passive"))
      (node (ref "R405") (pin "1") (pintype "passive"))
      (node (ref "R409") (pin "1") (pintype "passive"))
    )
    (net (code "68") (name "Net-(C360-Pad1)") (class "Default")
      (node (ref "C360") (pin "1") (pintype "passive"))
      (node (ref "R406") (pin "1") (pintype "passive"))
      (node (ref "R410") (pin "1") (pintype "passive"))
    )
    (net (code "69") (name "Net-(R363-Pad2)") (class "Default")
      (node (ref "R363") (pin "2") (pintype "passive"))
      (node (ref "XS5") (pin "A2") (pintype "passive"))
    )
    (net (code "70") (name "Net-(R364-Pad2)") (class "Default")
      (node (ref "R364") (pin "2") (pintype "passive"))
      (node (ref "XS5") (pin "C30") (pintype "passive"))
    )
    (net (code "71") (name "Net-(R365-Pad2)") (class "Default")
      (node (ref "R365") (pin "2") (pintype "passive"))
      (node (ref "XS5") (pin "E58") (pintype "passive"))
    )
    (net (code "72") (name "Net-(R366-Pad2)") (class "Default")
      (node (ref "R366") (pin "2") (pintype "passive"))
      (node (ref "XS5") (pin "G86") (pintype "passive"))
    )
    (net (code "73") (name "Net-(R367-Pad2)") (class "Default")
      (node (ref "R367") (pin "2") (pintype "passive"))
      (node (ref "XS5") (pin "A4") (pintype "passive"))
    )
    (net (code "74") (name "Net-(R368-Pad2)") (class "Default")
      (node (ref "R368") (pin "2") (pintype "passive"))
      (node (ref "XS5") (pin "C32") (pintype "passive"))
    )
    (net (code "75") (name "Net-(R369-Pad2)") (class "Default")
      (node (ref "R369") (pin "2") (pintype "passive"))
      (node (ref "XS5") (pin "E60") (pintype "passive"))
    )
    (net (code "76") (name "Net-(R370-Pad2)") (class "Default")
      (node (ref "R370") (pin "2") (pintype "passive"))
      (node (ref "XS5") (pin "G88") (pintype "passive"))
    )
    (net (code "77") (name "Net-(R387-Pad2)") (class "Default")
      (node (ref "R387") (pin "2") (pintype "passive"))
      (node (ref "XS5") (pin "B16") (pintype "passive"))
    )
    (net (code "78") (name "Net-(R388-Pad2)") (class "Default")
      (node (ref "R388") (pin "2") (pintype "passive"))
      (node (ref "XS5") (pin "D44") (pintype "passive"))
    )
    (net (code "79") (name "Net-(R389-Pad2)") (class "Default")
      (node (ref "R389") (pin "2") (pintype "passive"))
      (node (ref "XS5") (pin "F72") (pintype "passive"))
    )
    (net (code "80") (name "Net-(R390-Pad2)") (class "Default")
      (node (ref "R390") (pin "2") (pintype "passive"))
      (node (ref "XS5") (pin "H100") (pintype "passive"))
    )
    (net (code "81") (name "Net-(R391-Pad2)") (class "Default")
      (node (ref "R391") (pin "2") (pintype "passive"))
      (node (ref "XS5") (pin "B18") (pintype "passive"))
    )
    (net (code "82") (name "Net-(R392-Pad2)") (class "Default")
      (node (ref "R392") (pin "2") (pintype "passive"))
      (node (ref "XS5") (pin "F74") (pintype "passive"))
    )
    (net (code "83") (name "Net-(R393-Pad2)") (class "Default")
      (node (ref "R393") (pin "2") (pintype "passive"))
      (node (ref "XS5") (pin "H102") (pintype "passive"))
    )
    (net (code "84") (name "Net-(R394-Pad2)") (class "Default")
      (node (ref "R394") (pin "2") (pintype "passive"))
      (node (ref "XS5") (pin "D46") (pintype "passive"))
    )
    (net (code "85") (name "unconnected-(XS5-Pad113)") (class "Default")
      (node (ref "XS5") (pin "113") (pintype "passive"))
    )
    (net (code "86") (name "unconnected-(XS5-Pad113)_1") (class "Default")
      (node (ref "XS5") (pin "113") (pintype "passive"))
    )
    (net (code "87") (name "unconnected-(XS5-Pad113)_2") (class "Default")
      (node (ref "XS5") (pin "113") (pintype "passive"))
    )
    (net (code "88") (name "unconnected-(XS5-Pad113)_3") (class "Default")
      (node (ref "XS5") (pin "113") (pintype "passive"))
    )
    (net (code "89") (name "unconnected-(XS5-Pad113)_4") (class "Default")
      (node (ref "XS5") (pin "113") (pintype "passive"))
    )
    (net (code "90") (name "unconnected-(XS5-Pad113)_5") (class "Default")
      (node (ref "XS5") (pin "113") (pintype "passive"))
    )
    (net (code "91") (name "unconnected-(XS5-Pad113)_6") (class "Default")
      (node (ref "XS5") (pin "113") (pintype "passive"))
    )
    (net (code "92") (name "unconnected-(XS5-Pad113)_7") (class "Default")
      (node (ref "XS5") (pin "113") (pintype "passive"))
    )
    (net (code "93") (name "unconnected-(XS5-Pad114)") (class "Default")
      (node (ref "XS5") (pin "114") (pintype "passive"))
    )
    (net (code "94") (name "unconnected-(XS5-Pad114)_1") (class "Default")
      (node (ref "XS5") (pin "114") (pintype "passive"))
    )
    (net (code "95") (name "unconnected-(XS5-Pad114)_2") (class "Default")
      (node (ref "XS5") (pin "114") (pintype "passive"))
    )
    (net (code "96") (name "unconnected-(XS5-Pad114)_3") (class "Default")
      (node (ref "XS5") (pin "114") (pintype "passive"))
    )
    (net (code "97") (name "unconnected-(XS5-Pad114)_4") (class "Default")
      (node (ref "XS5") (pin "114") (pintype "passive"))
    )
    (net (code "98") (name "unconnected-(XS5-Pad114)_5") (class "Default")
      (node (ref "XS5") (pin "114") (pintype "passive"))
    )
    (net (code "99") (name "unconnected-(XS5-Pad114)_6") (class "Default")
      (node (ref "XS5") (pin "114") (pintype "passive"))
    )
    (net (code "100") (name "unconnected-(XS5-Pad114)_7") (class "Default")
      (node (ref "XS5") (pin "114") (pintype "passive"))
    )
    (net (code "101") (name "unconnected-(XS5-Pad115)") (class "Default")
      (node (ref "XS5") (pin "115") (pintype "passive"))
    )
    (net (code "102") (name "unconnected-(XS5-Pad115)_1") (class "Default")
      (node (ref "XS5") (pin "115") (pintype "passive"))
    )
    (net (code "103") (name "unconnected-(XS5-Pad115)_2") (class "Default")
      (node (ref "XS5") (pin "115") (pintype "passive"))
    )
    (net (code "104") (name "unconnected-(XS5-Pad115)_3") (class "Default")
      (node (ref "XS5") (pin "115") (pintype "passive"))
    )
    (net (code "105") (name "unconnected-(XS5-Pad115)_4") (class "Default")
      (node (ref "XS5") (pin "115") (pintype "passive"))
    )
    (net (code "106") (name "unconnected-(XS5-Pad115)_5") (class "Default")
      (node (ref "XS5") (pin "115") (pintype "passive"))
    )
    (net (code "107") (name "unconnected-(XS5-Pad115)_6") (class "Default")
      (node (ref "XS5") (pin "115") (pintype "passive"))
    )
    (net (code "108") (name "unconnected-(XS5-Pad115)_7") (class "Default")
      (node (ref "XS5") (pin "115") (pintype "passive"))
    )
    (net (code "109") (name "unconnected-(XS5-Pad116)") (class "Default")
      (node (ref "XS5") (pin "116") (pintype "passive"))
    )
    (net (code "110") (name "unconnected-(XS5-Pad116)_1") (class "Default")
      (node (ref "XS5") (pin "116") (pintype "passive"))
    )
    (net (code "111") (name "unconnected-(XS5-Pad116)_2") (class "Default")
      (node (ref "XS5") (pin "116") (pintype "passive"))
    )
    (net (code "112") (name "unconnected-(XS5-Pad116)_3") (class "Default")
      (node (ref "XS5") (pin "116") (pintype "passive"))
    )
    (net (code "113") (name "unconnected-(XS5-Pad116)_4") (class "Default")
      (node (ref "XS5") (pin "116") (pintype "passive"))
    )
    (net (code "114") (name "unconnected-(XS5-Pad116)_5") (class "Default")
      (node (ref "XS5") (pin "116") (pintype "passive"))
    )
    (net (code "115") (name "unconnected-(XS5-Pad116)_6") (class "Default")
      (node (ref "XS5") (pin "116") (pintype "passive"))
    )
    (net (code "116") (name "unconnected-(XS5-Pad116)_7") (class "Default")
      (node (ref "XS5") (pin "116") (pintype "passive"))
    )
    (net (code "117") (name "unconnected-(XS5-Pad116)_8") (class "Default")
      (node (ref "XS5") (pin "116") (pintype "passive"))
    )
    (net (code "118") (name "unconnected-(XS5-Pad117)") (class "Default")
      (node (ref "XS5") (pin "117") (pintype "passive"))
    )
    (net (code "119") (name "unconnected-(XS5-Pad117)_1") (class "Default")
      (node (ref "XS5") (pin "117") (pintype "passive"))
    )
    (net (code "120") (name "unconnected-(XS5-Pad117)_2") (class "Default")
      (node (ref "XS5") (pin "117") (pintype "passive"))
    )
    (net (code "121") (name "unconnected-(XS5-Pad117)_3") (class "Default")
      (node (ref "XS5") (pin "117") (pintype "passive"))
    )
    (net (code "122") (name "unconnected-(XS5-Pad117)_4") (class "Default")
      (node (ref "XS5") (pin "117") (pintype "passive"))
    )
    (net (code "123") (name "unconnected-(XS5-Pad117)_5") (class "Default")
      (node (ref "XS5") (pin "117") (pintype "passive"))
    )
    (net (code "124") (name "unconnected-(XS5-Pad117)_6") (class "Default")
      (node (ref "XS5") (pin "117") (pintype "passive"))
    )
    (net (code "125") (name "unconnected-(XS5-Pad117)_7") (class "Default")
      (node (ref "XS5") (pin "117") (pintype "passive"))
    )
    (net (code "126") (name "unconnected-(XS5-Pad117)_8") (class "Default")
      (node (ref "XS5") (pin "117") (pintype "passive"))
    )
    (net (code "127") (name "unconnected-(XS5-Pad118)") (class "Default")
      (node (ref "XS5") (pin "118") (pintype "passive"))
    )
    (net (code "128") (name "unconnected-(XS5-Pad118)_1") (class "Default")
      (node (ref "XS5") (pin "118") (pintype "passive"))
    )
    (net (code "129") (name "unconnected-(XS5-Pad118)_2") (class "Default")
      (node (ref "XS5") (pin "118") (pintype "passive"))
    )
    (net (code "130") (name "unconnected-(XS5-Pad118)_3") (class "Default")
      (node (ref "XS5") (pin "118") (pintype "passive"))
    )
    (net (code "131") (name "unconnected-(XS5-Pad118)_4") (class "Default")
      (node (ref "XS5") (pin "118") (pintype "passive"))
    )
    (net (code "132") (name "unconnected-(XS5-Pad118)_5") (class "Default")
      (node (ref "XS5") (pin "118") (pintype "passive"))
    )
    (net (code "133") (name "unconnected-(XS5-Pad118)_6") (class "Default")
      (node (ref "XS5") (pin "118") (pintype "passive"))
    )
    (net (code "134") (name "unconnected-(XS5-Pad118)_7") (class "Default")
      (node (ref "XS5") (pin "118") (pintype "passive"))
    )
    (net (code "135") (name "unconnected-(XS5-Pad118)_8") (class "Default")
      (node (ref "XS5") (pin "118") (pintype "passive"))
    )
    (net (code "136") (name "unconnected-(XS5-Pad119)") (class "Default")
      (node (ref "XS5") (pin "119") (pintype "passive"))
    )
    (net (code "137") (name "unconnected-(XS5-Pad119)_1") (class "Default")
      (node (ref "XS5") (pin "119") (pintype "passive"))
    )
    (net (code "138") (name "unconnected-(XS5-Pad119)_2") (class "Default")
      (node (ref "XS5") (pin "119") (pintype "passive"))
    )
    (net (code "139") (name "unconnected-(XS5-Pad119)_3") (class "Default")
      (node (ref "XS5") (pin "119") (pintype "passive"))
    )
    (net (code "140") (name "unconnected-(XS5-Pad119)_4") (class "Default")
      (node (ref "XS5") (pin "119") (pintype "passive"))
    )
    (net (code "141") (name "unconnected-(XS5-Pad119)_5") (class "Default")
      (node (ref "XS5") (pin "119") (pintype "passive"))
    )
    (net (code "142") (name "unconnected-(XS5-Pad119)_6") (class "Default")
      (node (ref "XS5") (pin "119") (pintype "passive"))
    )
    (net (code "143") (name "unconnected-(XS5-Pad119)_7") (class "Default")
      (node (ref "XS5") (pin "119") (pintype "passive"))
    )
    (net (code "144") (name "unconnected-(XS5-Pad120)") (class "Default")
      (node (ref "XS5") (pin "120") (pintype "passive"))
    )
    (net (code "145") (name "unconnected-(XS5-Pad120)_1") (class "Default")
      (node (ref "XS5") (pin "120") (pintype "passive"))
    )
    (net (code "146") (name "unconnected-(XS5-Pad120)_2") (class "Default")
      (node (ref "XS5") (pin "120") (pintype "passive"))
    )
    (net (code "147") (name "unconnected-(XS5-Pad120)_3") (class "Default")
      (node (ref "XS5") (pin "120") (pintype "passive"))
    )
    (net (code "148") (name "unconnected-(XS5-Pad120)_4") (class "Default")
      (node (ref "XS5") (pin "120") (pintype "passive"))
    )
    (net (code "149") (name "unconnected-(XS5-Pad120)_5") (class "Default")
      (node (ref "XS5") (pin "120") (pintype "passive"))
    )
    (net (code "150") (name "unconnected-(XS5-Pad120)_6") (class "Default")
      (node (ref "XS5") (pin "120") (pintype "passive"))
    )
    (net (code "151") (name "unconnected-(XS5-Pad120)_7") (class "Default")
      (node (ref "XS5") (pin "120") (pintype "passive"))
    )
    (net (code "152") (name "unconnected-(XS5-Pad121)") (class "Default")
      (node (ref "XS5") (pin "121") (pintype "passive"))
    )
    (net (code "153") (name "unconnected-(XS5-Pad121)_1") (class "Default")
      (node (ref "XS5") (pin "121") (pintype "passive"))
    )
    (net (code "154") (name "unconnected-(XS5-Pad121)_2") (class "Default")
      (node (ref "XS5") (pin "121") (pintype "passive"))
    )
    (net (code "155") (name "unconnected-(XS5-Pad121)_3") (class "Default")
      (node (ref "XS5") (pin "121") (pintype "passive"))
    )
    (net (code "156") (name "unconnected-(XS5-Pad121)_4") (class "Default")
      (node (ref "XS5") (pin "121") (pintype "passive"))
    )
    (net (code "157") (name "unconnected-(XS5-Pad121)_5") (class "Default")
      (node (ref "XS5") (pin "121") (pintype "passive"))
    )
    (net (code "158") (name "unconnected-(XS5-Pad121)_6") (class "Default")
      (node (ref "XS5") (pin "121") (pintype "passive"))
    )
    (net (code "159") (name "unconnected-(XS5-Pad121)_7") (class "Default")
      (node (ref "XS5") (pin "121") (pintype "passive"))
    )
    (net (code "160") (name "unconnected-(XS5-PadA11)") (class "Default")
      (node (ref "XS5") (pin "A11") (pintype "passive"))
    )
    (net (code "161") (name "unconnected-(XS5-PadA12)") (class "Default")
      (node (ref "XS5") (pin "A12") (pintype "passive"))
    )
    (net (code "162") (name "unconnected-(XS5-PadA13)") (class "Default")
      (node (ref "XS5") (pin "A13") (pintype "passive"))
    )
    (net (code "163") (name "unconnected-(XS5-PadA14)") (class "Default")
      (node (ref "XS5") (pin "A14") (pintype "passive"))
    )
    (net (code "164") (name "unconnected-(XS5-PadB25)") (class "Default")
      (node (ref "XS5") (pin "B25") (pintype "passive"))
    )
    (net (code "165") (name "unconnected-(XS5-PadB26)") (class "Default")
      (node (ref "XS5") (pin "B26") (pintype "passive"))
    )
    (net (code "166") (name "unconnected-(XS5-PadB27)") (class "Default")
      (node (ref "XS5") (pin "B27") (pintype "passive"))
    )
    (net (code "167") (name "unconnected-(XS5-PadB28)") (class "Default")
      (node (ref "XS5") (pin "B28") (pintype "passive"))
    )
    (net (code "168") (name "unconnected-(XS5-PadC39)") (class "Default")
      (node (ref "XS5") (pin "C39") (pintype "passive"))
    )
    (net (code "169") (name "unconnected-(XS5-PadC40)") (class "Default")
      (node (ref "XS5") (pin "C40") (pintype "passive"))
    )
    (net (code "170") (name "unconnected-(XS5-PadC41)") (class "Default")
      (node (ref "XS5") (pin "C41") (pintype "passive"))
    )
    (net (code "171") (name "unconnected-(XS5-PadC42)") (class "Default")
      (node (ref "XS5") (pin "C42") (pintype "passive"))
    )
    (net (code "172") (name "unconnected-(XS5-PadD53)") (class "Default")
      (node (ref "XS5") (pin "D53") (pintype "passive"))
    )
    (net (code "173") (name "unconnected-(XS5-PadD54)") (class "Default")
      (node (ref "XS5") (pin "D54") (pintype "passive"))
    )
    (net (code "174") (name "unconnected-(XS5-PadD55)") (class "Default")
      (node (ref "XS5") (pin "D55") (pintype "passive"))
    )
    (net (code "175") (name "unconnected-(XS5-PadD56)") (class "Default")
      (node (ref "XS5") (pin "D56") (pintype "passive"))
    )
    (net (code "176") (name "unconnected-(XS5-PadE67)") (class "Default")
      (node (ref "XS5") (pin "E67") (pintype "passive"))
    )
    (net (code "177") (name "unconnected-(XS5-PadE68)") (class "Default")
      (node (ref "XS5") (pin "E68") (pintype "passive"))
    )
    (net (code "178") (name "unconnected-(XS5-PadE69)") (class "Default")
      (node (ref "XS5") (pin "E69") (pintype "passive"))
    )
    (net (code "179") (name "unconnected-(XS5-PadE70)") (class "Default")
      (node (ref "XS5") (pin "E70") (pintype "passive"))
    )
    (net (code "180") (name "unconnected-(XS5-PadF81)") (class "Default")
      (node (ref "XS5") (pin "F81") (pintype "passive"))
    )
    (net (code "181") (name "unconnected-(XS5-PadF82)") (class "Default")
      (node (ref "XS5") (pin "F82") (pintype "passive"))
    )
    (net (code "182") (name "unconnected-(XS5-PadF83)") (class "Default")
      (node (ref "XS5") (pin "F83") (pintype "passive"))
    )
    (net (code "183") (name "unconnected-(XS5-PadF84)") (class "Default")
      (node (ref "XS5") (pin "F84") (pintype "passive"))
    )
    (net (code "184") (name "unconnected-(XS5-PadG95)") (class "Default")
      (node (ref "XS5") (pin "G95") (pintype "passive"))
    )
    (net (code "185") (name "unconnected-(XS5-PadG96)") (class "Default")
      (node (ref "XS5") (pin "G96") (pintype "passive"))
    )
    (net (code "186") (name "unconnected-(XS5-PadG97)") (class "Default")
      (node (ref "XS5") (pin "G97") (pintype "passive"))
    )
    (net (code "187") (name "unconnected-(XS5-PadG98)") (class "Default")
      (node (ref "XS5") (pin "G98") (pintype "passive"))
    )
    (net (code "188") (name "unconnected-(XS5-PadH109)") (class "Default")
      (node (ref "XS5") (pin "H109") (pintype "passive"))
    )
    (net (code "189") (name "unconnected-(XS5-PadH110)") (class "Default")
      (node (ref "XS5") (pin "H110") (pintype "passive"))
    )
    (net (code "190") (name "unconnected-(XS5-PadH111)") (class "Default")
      (node (ref "XS5") (pin "H111") (pintype "passive"))
    )
    (net (code "191") (name "unconnected-(XS5-PadH112)") (class "Default")
      (node (ref "XS5") (pin "H112") (pintype "passive"))
    )
  )
)
